# FMC_connector_CD.net
KiCad netlist of a schematic drawn in Altium Designer
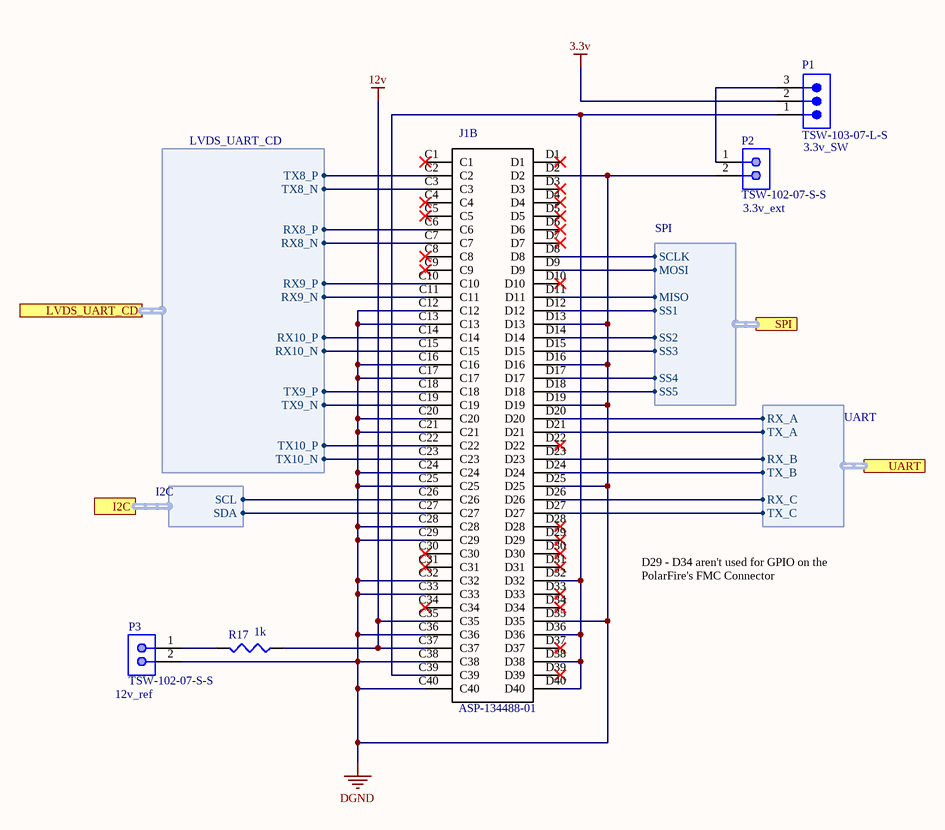
[diagram p0: FMC_connector_CD.SchDoc]

(export (version "E")
  (design (tool "Eeschema 10.0.6"))
  (components
    (comp (ref "J1")
      (value "ASP-134488-01")
      (footprint "*SAMTEC_ASP-134488-01_ASP-134488-01(Primary)")
      (description "Male FMC HPC Connector")
      (libsource (lib "Components") (part "ASP-134488-01"))
    )
    (comp (ref "P1")
      (value "TSW-103-07-L-S")
      (footprint "SMTC-TSW-103-07-X-S")
      (description "0.025\" SQ Post Header, Through-hole, Vertical, -55 to 125 degC, 2.54 mm Pitch, 3-Pin, Male, RoHS")
      (fields (field (name "MANUFACTURER") "Samtec"))
      (libsource (lib "Altium Content Vault") (part "SMTC-TSW-103-X-X-S-X"))
    )
    (comp (ref "P2")
      (value "TSW-102-07-S-S")
      (footprint "SMTC-TSW-102-07-S-S")
      (fields (field (name "MANUFACTURER") "Samtec"))
      (libsource (lib "") (part "CN-1P-M-R2_1"))
    )
    (comp (ref "P3")
      (value "TSW-102-07-S-S")
      (footprint "SMTC-TSW-102-07-S-S")
      (fields (field (name "MANUFACTURER") "Samtec"))
      (libsource (lib "Altium Content Vault") (part "CN-1P-M-R2"))
    )
    (comp (ref "R17")
      (value "1k")
      (footprint "J1-0603")
      (description "Resistor")
      (fields (field (name "Comment") "Res3") (field (name "PUBLISHER") "Altium Limited"))
      (libsource (lib "Miscellaneous Devices") (part "Res3"))
    )
  )
  (nets
    (net (code "5") (name "/MISO") (class "Default")
      (node (ref "J1") (pin "D11") (pinfunction "D11_D11") (pintype "passive"))
    )
    (net (code "6") (name "/MOSI") (class "Default")
      (node (ref "J1") (pin "D9") (pinfunction "D9_D9") (pintype "passive"))
    )
    (net (code "7") (name "/RX8_N") (class "Default")
      (node (ref "J1") (pin "C7") (pinfunction "C7_C7") (pintype "passive"))
    )
    (net (code "8") (name "/RX8_P") (class "Default")
      (node (ref "J1") (pin "C6") (pinfunction "C6_C6") (pintype "passive"))
    )
    (net (code "9") (name "/RX9_N") (class "Default")
      (node (ref "J1") (pin "C11") (pinfunction "C11_C11") (pintype "passive"))
    )
    (net (code "10") (name "/RX9_P") (class "Default")
      (node (ref "J1") (pin "C10") (pinfunction "C10_C10") (pintype "passive"))
    )
    (net (code "11") (name "/RX10_N") (class "Default")
      (node (ref "J1") (pin "C15") (pinfunction "C15_C15") (pintype "passive"))
    )
    (net (code "12") (name "/RX10_P") (class "Default")
      (node (ref "J1") (pin "C14") (pinfunction "C14_C14") (pintype "passive"))
    )
    (net (code "13") (name "/RX_A") (class "Default")
      (node (ref "J1") (pin "D20") (pinfunction "D20_D20") (pintype "passive"))
    )
    (net (code "14") (name "/RX_B") (class "Default")
      (node (ref "J1") (pin "D23") (pinfunction "D23_D23") (pintype "passive"))
    )
    (net (code "15") (name "/RX_C") (class "Default")
      (node (ref "J1") (pin "D26") (pinfunction "D26_D26") (pintype "passive"))
    )
    (net (code "16") (name "/SCL") (class "Default")
      (node (ref "J1") (pin "C26") (pinfunction "C26_C26") (pintype "passive"))
    )
    (net (code "17") (name "/SCLK") (class "Default")
      (node (ref "J1") (pin "D8") (pinfunction "D8_D8") (pintype "passive"))
    )
    (net (code "18") (name "/SDA") (class "Default")
      (node (ref "J1") (pin "C27") (pinfunction "C27_C27") (pintype "passive"))
    )
    (net (code "19") (name "/SS1") (class "Default")
      (node (ref "J1") (pin "D12") (pinfunction "D12_D12") (pintype "passive"))
    )
    (net (code "20") (name "/SS2") (class "Default")
      (node (ref "J1") (pin "D14") (pinfunction "D14_D14") (pintype "passive"))
    )
    (net (code "21") (name "/SS3") (class "Default")
      (node (ref "J1") (pin "D15") (pinfunction "D15_D15") (pintype "passive"))
    )
    (net (code "22") (name "/SS4") (class "Default")
      (node (ref "J1") (pin "D17") (pinfunction "D17_D17") (pintype "passive"))
    )
    (net (code "23") (name "/SS5") (class "Default")
      (node (ref "J1") (pin "D18") (pinfunction "D18_D18") (pintype "passive"))
    )
    (net (code "24") (name "/TX8_N") (class "Default")
      (node (ref "J1") (pin "C3") (pinfunction "C3_C3") (pintype "passive"))
    )
    (net (code "25") (name "/TX8_P") (class "Default")
      (node (ref "J1") (pin "C2") (pinfunction "C2_C2") (pintype "passive"))
    )
    (net (code "26") (name "/TX9_N") (class "Default")
      (node (ref "J1") (pin "C19") (pinfunction "C19_C19") (pintype "passive"))
    )
    (net (code "27") (name "/TX9_P") (class "Default")
      (node (ref "J1") (pin "C18") (pinfunction "C18_C18") (pintype "passive"))
    )
    (net (code "28") (name "/TX10_N") (class "Default")
      (node (ref "J1") (pin "C23") (pinfunction "C23_C23") (pintype "passive"))
    )
    (net (code "29") (name "/TX10_P") (class "Default")
      (node (ref "J1") (pin "C22") (pinfunction "C22_C22") (pintype "passive"))
    )
    (net (code "30") (name "/TX_A") (class "Default")
      (node (ref "J1") (pin "D21") (pinfunction "D21_D21") (pintype "passive"))
    )
    (net (code "31") (name "/TX_B") (class "Default")
      (node (ref "J1") (pin "D24") (pinfunction "D24_D24") (pintype "passive"))
    )
    (net (code "32") (name "/TX_C") (class "Default")
      (node (ref "J1") (pin "D27") (pinfunction "D27_D27") (pintype "passive"))
    )
    (net (code "37") (name "3.3v") (class "Default")
      (node (ref "P1") (pin "2") (pinfunction "2_2") (pintype "passive"))
    )
    (net (code "38") (name "12v") (class "Default")
      (node (ref "J1") (pin "C35") (pinfunction "C35_C35") (pintype "passive"))
      (node (ref "J1") (pin "C37") (pinfunction "C37_C37") (pintype "passive"))
      (node (ref "R17") (pin "1") (pinfunction "1_1") (pintype "passive"))
    )
    (net (code "39") (name "DGND") (class "Default")
      (node (ref "J1") (pin "C12") (pinfunction "C12_C12") (pintype "passive"))
      (node (ref "J1") (pin "C13") (pinfunction "C13_C13") (pintype "passive"))
      (node (ref "J1") (pin "C16") (pinfunction "C16_C16") (pintype "passive"))
      (node (ref "J1") (pin "C17") (pinfunction "C17_C17") (pintype "passive"))
      (node (ref "J1") (pin "C20") (pinfunction "C20_C20") (pintype "passive"))
      (node (ref "J1") (pin "C21") (pinfunction "C21_C21") (pintype "passive"))
      (node (ref "J1") (pin "C24") (pinfunction "C24_C24") (pintype "passive"))
      (node (ref "J1") (pin "C25") (pinfunction "C25_C25") (pintype "passive"))
      (node (ref "J1") (pin "C28") (pinfunction "C28_C28") (pintype "passive"))
      (node (ref "J1") (pin "C29") (pinfunction "C29_C29") (pintype "passive"))
      (node (ref "J1") (pin "C32") (pinfunction "C32_C32") (pintype "passive"))
      (node (ref "J1") (pin "C33") (pinfunction "C33_C33") (pintype "passive"))
      (node (ref "J1") (pin "C36") (pinfunction "C36_C36") (pintype "passive"))
      (node (ref "J1") (pin "C38") (pinfunction "C38_C38") (pintype "passive"))
      (node (ref "J1") (pin "C40") (pinfunction "C40_C40") (pintype "passive"))
      (node (ref "J1") (pin "D13") (pinfunction "D13_D13") (pintype "passive"))
      (node (ref "J1") (pin "D16") (pinfunction "D16_D16") (pintype "passive"))
      (node (ref "J1") (pin "D19") (pinfunction "D19_D19") (pintype "passive"))
      (node (ref "J1") (pin "D2") (pinfunction "D2_D2") (pintype "passive"))
      (node (ref "J1") (pin "D25") (pinfunction "D25_D25") (pintype "passive"))
      (node (ref "J1") (pin "D35") (pinfunction "D35_D35") (pintype "passive"))
      (node (ref "P2") (pin "2") (pinfunction "2_2") (pintype "passive"))
      (node (ref "P3") (pin "2") (pinfunction "2_2") (pintype "passive"))
    )
    (net (code "40") (name "Net-(J1-PadC39)") (class "Default")
      (node (ref "J1") (pin "C39") (pinfunction "C39_C39") (pintype "passive"))
      (node (ref "J1") (pin "D32") (pinfunction "D32_D32") (pintype "passive"))
      (node (ref "J1") (pin "D36") (pinfunction "D36_D36") (pintype "passive"))
      (node (ref "J1") (pin "D38") (pinfunction "D38_D38") (pintype "passive"))
      (node (ref "J1") (pin "D40") (pinfunction "D40_D40") (pintype "passive"))
      (node (ref "P1") (pin "1") (pinfunction "1_1") (pintype "passive"))
    )
    (net (code "41") (name "Net-(P1-Pad3)") (class "Default")
      (node (ref "P1") (pin "3") (pinfunction "3_3") (pintype "passive"))
      (node (ref "P2") (pin "1") (pinfunction "1_1") (pintype "passive"))
    )
    (net (code "42") (name "Net-(P3-Pad1)") (class "Default")
      (node (ref "P3") (pin "1") (pinfunction "1_1") (pintype "passive"))
      (node (ref "R17") (pin "2") (pinfunction "2_2") (pintype "passive"))
    )
    (net (code "43") (name "unconnected-(J1-PadC1)") (class "Default")
      (node (ref "J1") (pin "C1") (pinfunction "C1_C1") (pintype "passive+no_connect"))
    )
    (net (code "44") (name "unconnected-(J1-PadC4)") (class "Default")
      (node (ref "J1") (pin "C4") (pinfunction "C4_C4") (pintype "passive+no_connect"))
    )
    (net (code "45") (name "unconnected-(J1-PadC5)") (class "Default")
      (node (ref "J1") (pin "C5") (pinfunction "C5_C5") (pintype "passive+no_connect"))
    )
    (net (code "46") (name "unconnected-(J1-PadC8)") (class "Default")
      (node (ref "J1") (pin "C8") (pinfunction "C8_C8") (pintype "passive+no_connect"))
    )
    (net (code "47") (name "unconnected-(J1-PadC9)") (class "Default")
      (node (ref "J1") (pin "C9") (pinfunction "C9_C9") (pintype "passive+no_connect"))
    )
    (net (code "48") (name "unconnected-(J1-PadC30)") (class "Default")
      (node (ref "J1") (pin "C30") (pinfunction "C30_C30") (pintype "passive+no_connect"))
    )
    (net (code "49") (name "unconnected-(J1-PadC31)") (class "Default")
      (node (ref "J1") (pin "C31") (pinfunction "C31_C31") (pintype "passive+no_connect"))
    )
    (net (code "50") (name "unconnected-(J1-PadC34)") (class "Default")
      (node (ref "J1") (pin "C34") (pinfunction "C34_C34") (pintype "passive+no_connect"))
    )
    (net (code "51") (name "unconnected-(J1-PadD1)") (class "Default")
      (node (ref "J1") (pin "D1") (pinfunction "D1_D1") (pintype "passive+no_connect"))
    )
    (net (code "52") (name "unconnected-(J1-PadD3)") (class "Default")
      (node (ref "J1") (pin "D3") (pinfunction "D3_D3") (pintype "passive+no_connect"))
    )
    (net (code "53") (name "unconnected-(J1-PadD4)") (class "Default")
      (node (ref "J1") (pin "D4") (pinfunction "D4_D4") (pintype "passive+no_connect"))
    )
    (net (code "54") (name "unconnected-(J1-PadD5)") (class "Default")
      (node (ref "J1") (pin "D5") (pinfunction "D5_D5") (pintype "passive+no_connect"))
    )
    (net (code "55") (name "unconnected-(J1-PadD6)") (class "Default")
      (node (ref "J1") (pin "D6") (pinfunction "D6_D6") (pintype "passive+no_connect"))
    )
    (net (code "56") (name "unconnected-(J1-PadD7)") (class "Default")
      (node (ref "J1") (pin "D7") (pinfunction "D7_D7") (pintype "passive+no_connect"))
    )
    (net (code "57") (name "unconnected-(J1-PadD10)") (class "Default")
      (node (ref "J1") (pin "D10") (pinfunction "D10_D10") (pintype "passive+no_connect"))
    )
    (net (code "58") (name "unconnected-(J1-PadD22)") (class "Default")
      (node (ref "J1") (pin "D22") (pinfunction "D22_D22") (pintype "passive+no_connect"))
    )
    (net (code "59") (name "unconnected-(J1-PadD28)") (class "Default")
      (node (ref "J1") (pin "D28") (pinfunction "D28_D28") (pintype "passive+no_connect"))
    )
    (net (code "60") (name "unconnected-(J1-PadD29)") (class "Default")
      (node (ref "J1") (pin "D29") (pinfunction "D29_D29") (pintype "passive+no_connect"))
    )
    (net (code "61") (name "unconnected-(J1-PadD30)") (class "Default")
      (node (ref "J1") (pin "D30") (pinfunction "D30_D30") (pintype "passive+no_connect"))
    )
    (net (code "62") (name "unconnected-(J1-PadD31)") (class "Default")
      (node (ref "J1") (pin "D31") (pinfunction "D31_D31") (pintype "passive+no_connect"))
    )
    (net (code "63") (name "unconnected-(J1-PadD33)") (class "Default")
      (node (ref "J1") (pin "D33") (pinfunction "D33_D33") (pintype "passive+no_connect"))
    )
    (net (code "64") (name "unconnected-(J1-PadD34)") (class "Default")
      (node (ref "J1") (pin "D34") (pinfunction "D34_D34") (pintype "passive+no_connect"))
    )
    (net (code "65") (name "unconnected-(J1-PadD37)") (class "Default")
      (node (ref "J1") (pin "D37") (pinfunction "D37_D37") (pintype "passive+no_connect"))
    )
    (net (code "66") (name "unconnected-(J1-PadD39)") (class "Default")
      (node (ref "J1") (pin "D39") (pinfunction "D39_D39") (pintype "passive+no_connect"))
    )
  )
)
